# 14_NTC_TEMPSENSOR.net
KiCad netlist of a schematic drawn in Altium Designer
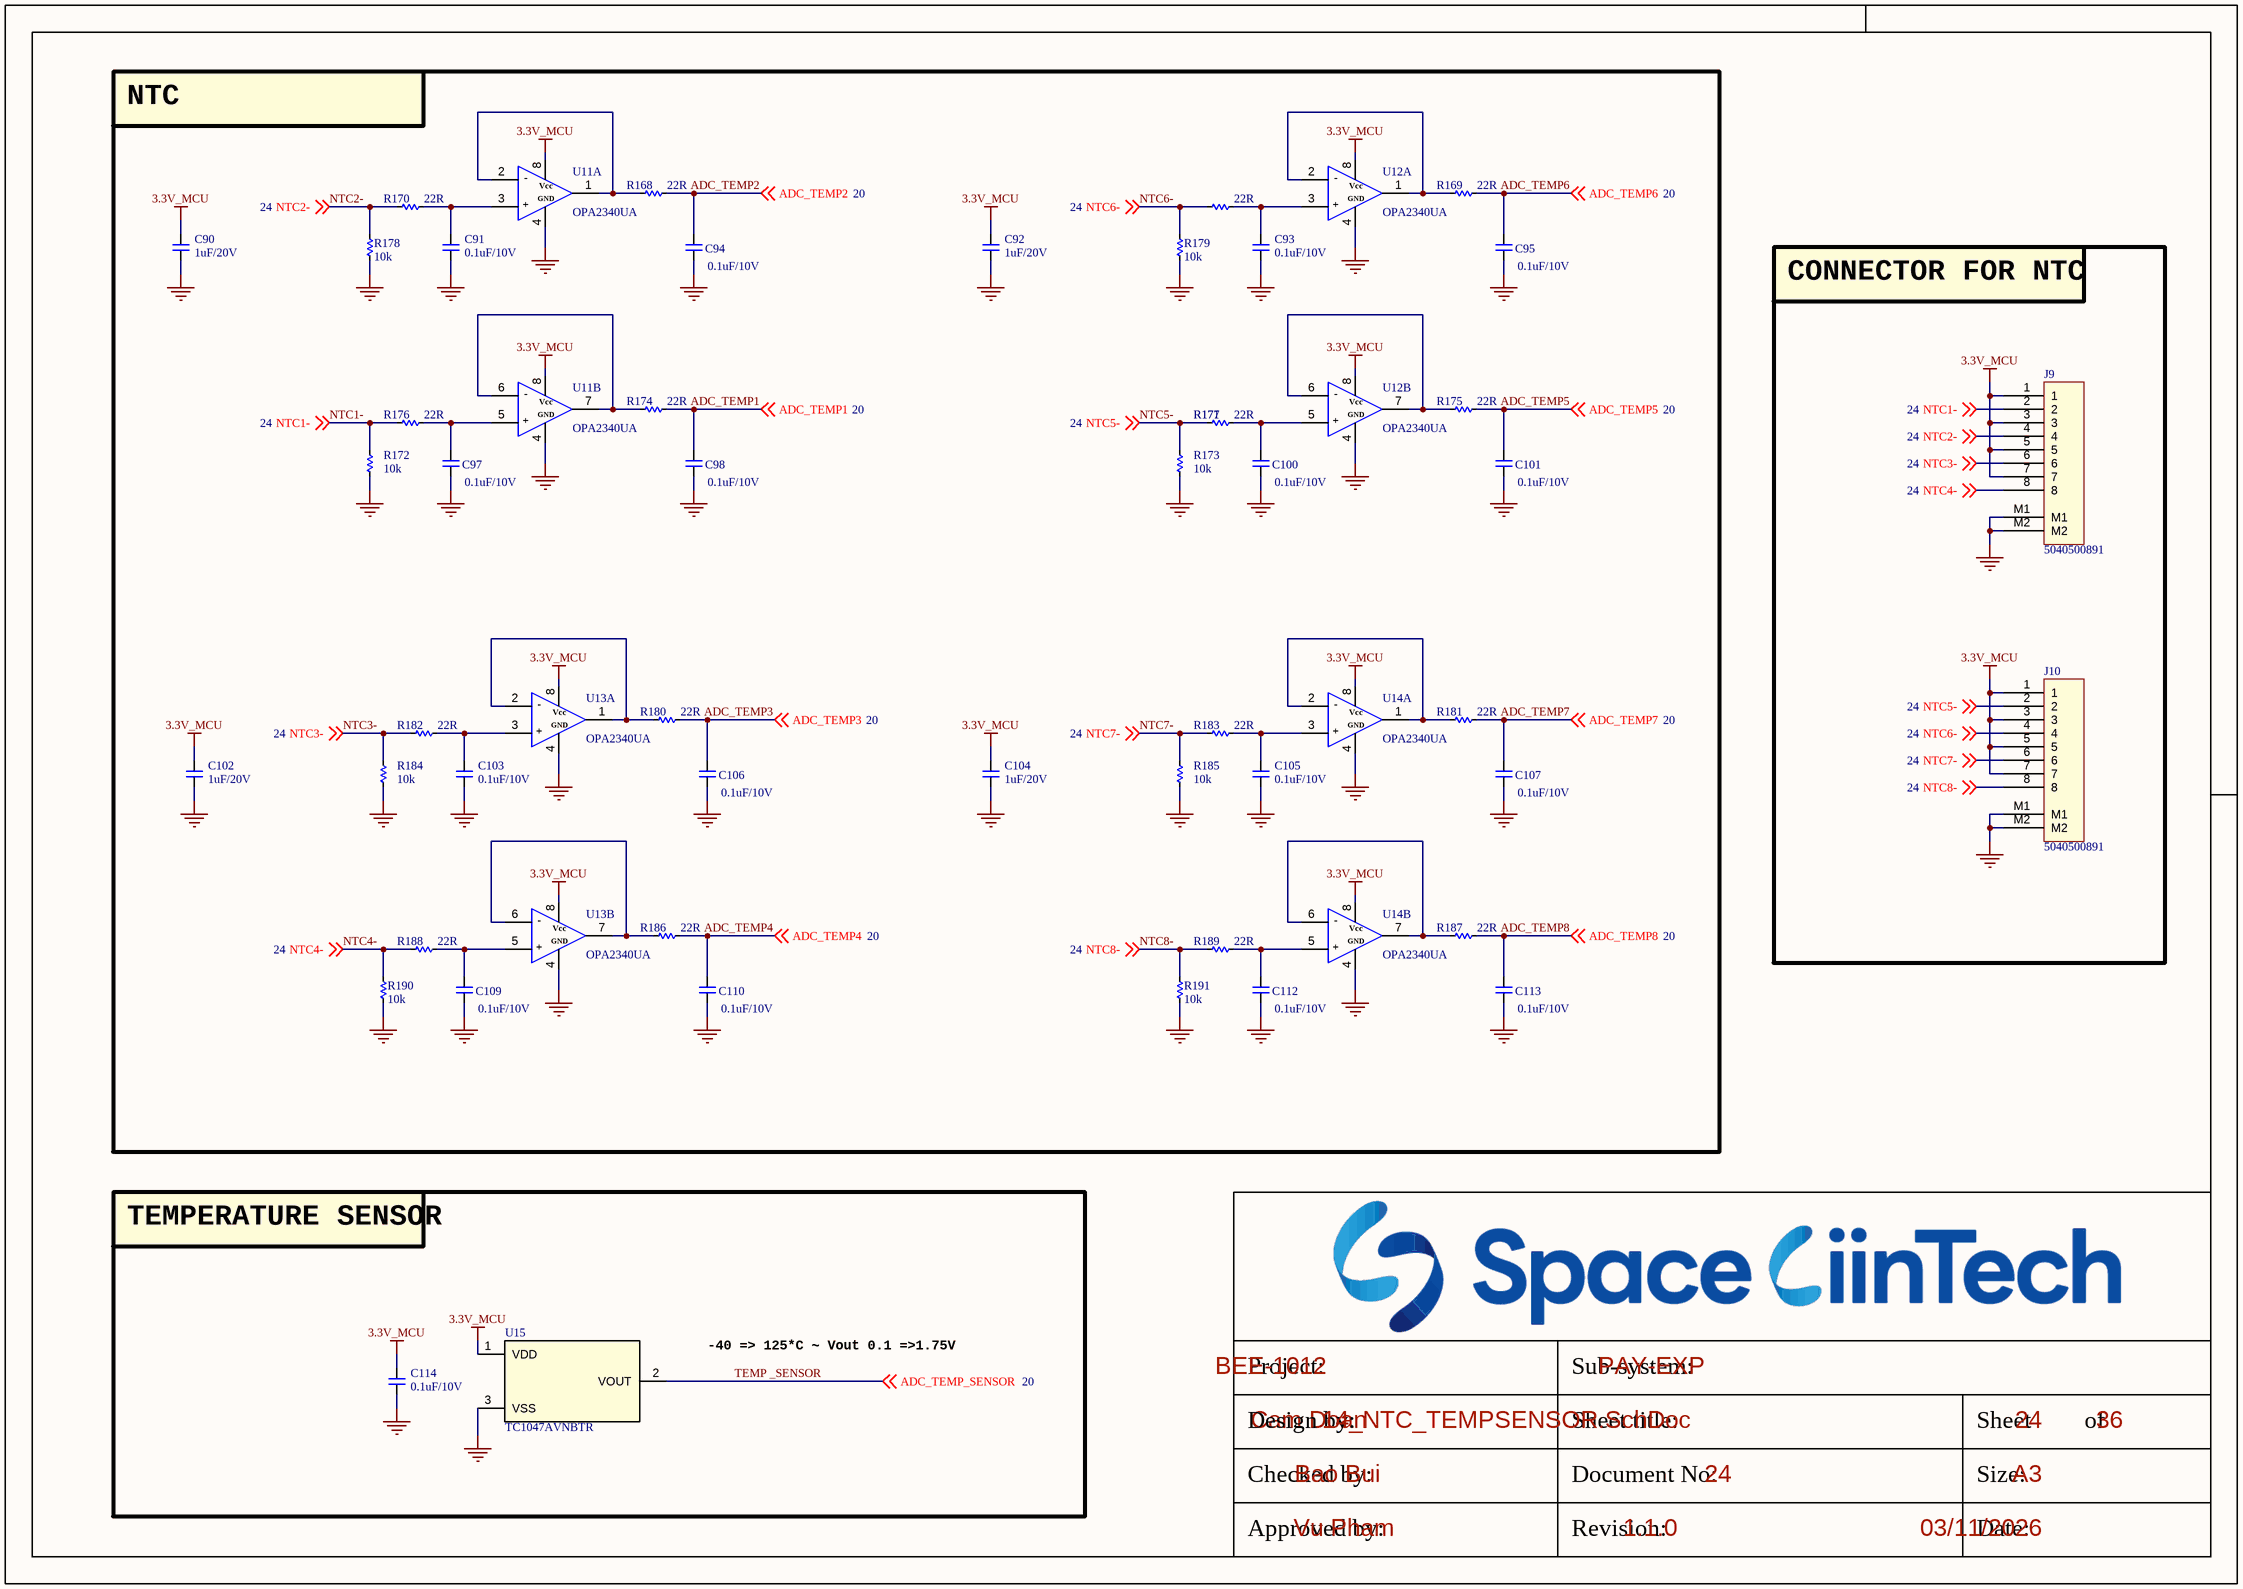
[diagram p0: 14_NTC_TEMPSENSOR.SchDoc]

(export (version "E")
  (design (tool "Eeschema 10.0.6"))
  (components
    (comp (ref "C90")
      (value "1uF/20V")
      (footprint "CAP_C_1005X50_L")
      (description "CAP")
      (libsource (lib "LABLIB") (part "_CAP_C_2"))
    )
    (comp (ref "C91")
      (value "0.1uF/10V")
      (footprint "CAP_C_1005X50_L")
      (description "CAP")
      (libsource (lib "LABLIB") (part "_CAP_C_2"))
    )
    (comp (ref "C92")
      (value "1uF/20V")
      (footprint "CAP_C_1005X50_L")
      (description "CAP")
      (libsource (lib "LABLIB") (part "_CAP_C_2"))
    )
    (comp (ref "C93")
      (value "0.1uF/10V")
      (footprint "CAP_C_1005X50_L")
      (description "CAP")
      (libsource (lib "LABLIB") (part "_CAP_C_2"))
    )
    (comp (ref "C94")
      (value "0.1uF/10V")
      (footprint "CAP_C_1005X50_L")
      (description "CAP")
      (libsource (lib "LABLIB") (part "_CAP_C_2"))
    )
    (comp (ref "C95")
      (value "0.1uF/10V")
      (footprint "CAP_C_1005X50_L")
      (description "CAP")
      (libsource (lib "LABLIB") (part "_CAP_C_2"))
    )
    (comp (ref "C97")
      (value "0.1uF/10V")
      (footprint "CAP_C_1005X50_L")
      (description "CAP")
      (libsource (lib "LABLIB") (part "_CAP_C_2"))
    )
    (comp (ref "C98")
      (value "0.1uF/10V")
      (footprint "CAP_C_1005X50_L")
      (description "CAP")
      (libsource (lib "LABLIB") (part "_CAP_C_2"))
    )
    (comp (ref "C100")
      (value "0.1uF/10V")
      (footprint "CAP_C_1005X50_L")
      (description "CAP")
      (libsource (lib "LABLIB") (part "_CAP_C_2"))
    )
    (comp (ref "C101")
      (value "0.1uF/10V")
      (footprint "CAP_C_1005X50_L")
      (description "CAP")
      (libsource (lib "LABLIB") (part "_CAP_C_2"))
    )
    (comp (ref "C102")
      (value "1uF/20V")
      (footprint "CAP_C_1005X50_L")
      (description "CAP")
      (libsource (lib "LABLIB") (part "_CAP_C_2"))
    )
    (comp (ref "C103")
      (value "0.1uF/10V")
      (footprint "CAP_C_1005X50_L")
      (description "CAP")
      (libsource (lib "LABLIB") (part "_CAP_C_2"))
    )
    (comp (ref "C104")
      (value "1uF/20V")
      (footprint "CAP_C_1005X50_L")
      (description "CAP")
      (libsource (lib "LABLIB") (part "_CAP_C_2"))
    )
    (comp (ref "C105")
      (value "0.1uF/10V")
      (footprint "CAP_C_1005X50_L")
      (description "CAP")
      (libsource (lib "LABLIB") (part "_CAP_C_2"))
    )
    (comp (ref "C106")
      (value "0.1uF/10V")
      (footprint "CAP_C_1005X50_L")
      (description "CAP")
      (libsource (lib "LABLIB") (part "_CAP_C_2"))
    )
    (comp (ref "C107")
      (value "0.1uF/10V")
      (footprint "CAP_C_1005X50_L")
      (description "CAP")
      (libsource (lib "LABLIB") (part "_CAP_C_2"))
    )
    (comp (ref "C109")
      (value "0.1uF/10V")
      (footprint "CAP_C_1005X50_L")
      (description "CAP")
      (libsource (lib "LABLIB") (part "_CAP_C_2"))
    )
    (comp (ref "C110")
      (value "0.1uF/10V")
      (footprint "CAP_C_1005X50_L")
      (description "CAP")
      (libsource (lib "LABLIB") (part "_CAP_C_2"))
    )
    (comp (ref "C112")
      (value "0.1uF/10V")
      (footprint "CAP_C_1005X50_L")
      (description "CAP")
      (libsource (lib "LABLIB") (part "_CAP_C_2"))
    )
    (comp (ref "C113")
      (value "0.1uF/10V")
      (footprint "CAP_C_1005X50_L")
      (description "CAP")
      (libsource (lib "LABLIB") (part "_CAP_C_2"))
    )
    (comp (ref "C114")
      (value "0.1uF/10V")
      (footprint "CAP_C_1005X50_L")
      (description "CAP")
      (libsource (lib "LABLIB") (part "_CAP_C_2"))
    )
    (comp (ref "J9")
      (value "5040500891")
      (footprint "MOLEX_5040500891")
      (libsource (lib "LABLIB") (part "Header 8x1_2M"))
    )
    (comp (ref "J10")
      (value "5040500891")
      (footprint "MOLEX_5040500891")
      (libsource (lib "LABLIB") (part "Header 8x1_2M"))
    )
    (comp (ref "R168")
      (value "22R")
      (footprint "RES_C_1005x30_L")
      (description "RES")
      (libsource (lib "LABLIB") (part "_RES_B_2"))
    )
    (comp (ref "R169")
      (value "22R")
      (footprint "RES_C_1005x30_L")
      (description "RES")
      (libsource (lib "LABLIB") (part "_RES_B_2"))
    )
    (comp (ref "R170")
      (value "22R")
      (footprint "RES_C_1005x30_L")
      (description "RES")
      (libsource (lib "LABLIB") (part "_RES_B_2"))
    )
    (comp (ref "R171")
      (value "22R")
      (footprint "RES_C_1005x30_L")
      (description "RES")
      (libsource (lib "LABLIB") (part "_RES_B_2"))
    )
    (comp (ref "R172")
      (value "10k")
      (footprint "RES_C_1005x30_L")
      (description "RES")
      (libsource (lib "LABLIB") (part "_RES_B_2"))
    )
    (comp (ref "R173")
      (value "10k")
      (footprint "RES_C_1005x30_L")
      (description "RES")
      (libsource (lib "LABLIB") (part "_RES_B_2"))
    )
    (comp (ref "R174")
      (value "22R")
      (footprint "RES_C_1005x30_L")
      (description "RES")
      (libsource (lib "LABLIB") (part "_RES_B_2"))
    )
    (comp (ref "R175")
      (value "22R")
      (footprint "RES_C_1005x30_L")
      (description "RES")
      (libsource (lib "LABLIB") (part "_RES_B_2"))
    )
    (comp (ref "R176")
      (value "22R")
      (footprint "RES_C_1005x30_L")
      (description "RES")
      (libsource (lib "LABLIB") (part "_RES_B_2"))
    )
    (comp (ref "R177")
      (value "22R")
      (footprint "RES_C_1005x30_L")
      (description "RES")
      (libsource (lib "LABLIB") (part "_RES_B_2"))
    )
    (comp (ref "R178")
      (value "10k")
      (footprint "RES_C_1005x30_L")
      (description "RES")
      (libsource (lib "LABLIB") (part "_RES_B_2"))
    )
    (comp (ref "R179")
      (value "10k")
      (footprint "RES_C_1005x30_L")
      (description "RES")
      (libsource (lib "LABLIB") (part "_RES_B_2"))
    )
    (comp (ref "R180")
      (value "22R")
      (footprint "RES_C_1005x30_L")
      (description "RES")
      (libsource (lib "LABLIB") (part "_RES_B_2"))
    )
    (comp (ref "R181")
      (value "22R")
      (footprint "RES_C_1005x30_L")
      (description "RES")
      (libsource (lib "LABLIB") (part "_RES_B_2"))
    )
    (comp (ref "R182")
      (value "22R")
      (footprint "RES_C_1005x30_L")
      (description "RES")
      (libsource (lib "LABLIB") (part "_RES_B_2"))
    )
    (comp (ref "R183")
      (value "22R")
      (footprint "RES_C_1005x30_L")
      (description "RES")
      (libsource (lib "LABLIB") (part "_RES_B_2"))
    )
    (comp (ref "R184")
      (value "10k")
      (footprint "RES_C_1005x30_L")
      (description "RES")
      (libsource (lib "LABLIB") (part "_RES_B_2"))
    )
    (comp (ref "R185")
      (value "10k")
      (footprint "RES_C_1005x30_L")
      (description "RES")
      (libsource (lib "LABLIB") (part "_RES_B_2"))
    )
    (comp (ref "R186")
      (value "22R")
      (footprint "RES_C_1005x30_L")
      (description "RES")
      (libsource (lib "LABLIB") (part "_RES_B_2"))
    )
    (comp (ref "R187")
      (value "22R")
      (footprint "RES_C_1005x30_L")
      (description "RES")
      (libsource (lib "LABLIB") (part "_RES_B_2"))
    )
    (comp (ref "R188")
      (value "22R")
      (footprint "RES_C_1005x30_L")
      (description "RES")
      (libsource (lib "LABLIB") (part "_RES_B_2"))
    )
    (comp (ref "R189")
      (value "22R")
      (footprint "RES_C_1005x30_L")
      (description "RES")
      (libsource (lib "LABLIB") (part "_RES_B_2"))
    )
    (comp (ref "R190")
      (value "10k")
      (footprint "RES_C_1005x30_L")
      (description "RES")
      (libsource (lib "LABLIB") (part "_RES_B_2"))
    )
    (comp (ref "R191")
      (value "10k")
      (footprint "RES_C_1005x30_L")
      (description "RES")
      (libsource (lib "LABLIB") (part "_RES_B_2"))
    )
    (comp (ref "U11")
      (value "OPA2340UA")
      (footprint "SOIC127P602X173-8N")
      (libsource (lib "EXP_HW_V3") (part "OPA2340UA"))
    )
    (comp (ref "U12")
      (value "OPA2340UA")
      (footprint "SOIC127P602X173-8N")
      (libsource (lib "EXP_HW_V3") (part "OPA2340UA"))
    )
    (comp (ref "U13")
      (value "OPA2340UA")
      (footprint "SOIC127P602X173-8N")
      (libsource (lib "EXP_HW_V3") (part "OPA2340UA"))
    )
    (comp (ref "U14")
      (value "OPA2340UA")
      (footprint "SOIC127P602X173-8N")
      (libsource (lib "EXP_HW_V3") (part "OPA2340UA"))
    )
    (comp (ref "U15")
      (value "TC1047AVNBTR")
      (footprint "SOT95P240X120-3N")
      (description "Temperature Sensor Analog, Local -40°C ~ 125°C 10mV/°C SOT-23-3")
      (libsource (lib "LABLIB") (part "IC_SENSOR_TC1047AVNBTR"))
    )
  )
  (nets
    (net (code "1") (name "3.3V_MCU") (class "Default")
      (node (ref "C102") (pin "2") (pinfunction "2_2") (pintype "passive"))
      (node (ref "C104") (pin "2") (pinfunction "2_2") (pintype "passive"))
      (node (ref "C114") (pin "2") (pinfunction "2_2") (pintype "passive"))
      (node (ref "C90") (pin "2") (pinfunction "2_2") (pintype "passive"))
      (node (ref "C92") (pin "2") (pinfunction "2_2") (pintype "passive"))
      (node (ref "J10") (pin "1") (pinfunction "1_1") (pintype "passive"))
      (node (ref "J10") (pin "3") (pinfunction "3_3") (pintype "passive"))
      (node (ref "J10") (pin "5") (pinfunction "5_5") (pintype "passive"))
      (node (ref "J10") (pin "7") (pinfunction "7_7") (pintype "passive"))
      (node (ref "J9") (pin "1") (pinfunction "1_1") (pintype "passive"))
      (node (ref "J9") (pin "3") (pinfunction "3_3") (pintype "passive"))
      (node (ref "J9") (pin "5") (pinfunction "5_5") (pintype "passive"))
      (node (ref "J9") (pin "7") (pinfunction "7_7") (pintype "passive"))
      (node (ref "U11") (pin "8") (pinfunction "8_8") (pintype "passive"))
      (node (ref "U12") (pin "8") (pinfunction "8_8") (pintype "passive"))
      (node (ref "U13") (pin "8") (pinfunction "8_8") (pintype "passive"))
      (node (ref "U14") (pin "8") (pinfunction "8_8") (pintype "passive"))
      (node (ref "U15") (pin "1") (pinfunction "VDD_1") (pintype "passive"))
    )
    (net (code "2") (name "ADC_TEMP1") (class "Default")
      (node (ref "C98") (pin "2") (pinfunction "2_2") (pintype "passive"))
      (node (ref "R174") (pin "2") (pinfunction "2_2") (pintype "passive"))
    )
    (net (code "3") (name "ADC_TEMP2") (class "Default")
      (node (ref "C94") (pin "2") (pinfunction "2_2") (pintype "passive"))
      (node (ref "R168") (pin "2") (pinfunction "2_2") (pintype "passive"))
    )
    (net (code "4") (name "ADC_TEMP3") (class "Default")
      (node (ref "C106") (pin "2") (pinfunction "2_2") (pintype "passive"))
      (node (ref "R180") (pin "2") (pinfunction "2_2") (pintype "passive"))
    )
    (net (code "5") (name "ADC_TEMP4") (class "Default")
      (node (ref "C110") (pin "2") (pinfunction "2_2") (pintype "passive"))
      (node (ref "R186") (pin "2") (pinfunction "2_2") (pintype "passive"))
    )
    (net (code "6") (name "ADC_TEMP5") (class "Default")
      (node (ref "C101") (pin "2") (pinfunction "2_2") (pintype "passive"))
      (node (ref "R175") (pin "2") (pinfunction "2_2") (pintype "passive"))
    )
    (net (code "7") (name "ADC_TEMP6") (class "Default")
      (node (ref "C95") (pin "2") (pinfunction "2_2") (pintype "passive"))
      (node (ref "R169") (pin "2") (pinfunction "2_2") (pintype "passive"))
    )
    (net (code "8") (name "ADC_TEMP7") (class "Default")
      (node (ref "C107") (pin "2") (pinfunction "2_2") (pintype "passive"))
      (node (ref "R181") (pin "2") (pinfunction "2_2") (pintype "passive"))
    )
    (net (code "9") (name "ADC_TEMP8") (class "Default")
      (node (ref "C113") (pin "2") (pinfunction "2_2") (pintype "passive"))
      (node (ref "R187") (pin "2") (pinfunction "2_2") (pintype "passive"))
    )
    (net (code "10") (name "ADC_TEMP_SENSOR") (class "Default")
      (node (ref "U15") (pin "2") (pinfunction "VOUT_2") (pintype "passive"))
    )
    (net (code "11") (name "GND") (class "Default")
      (node (ref "C100") (pin "1") (pinfunction "1_1") (pintype "passive"))
      (node (ref "C101") (pin "1") (pinfunction "1_1") (pintype "passive"))
      (node (ref "C102") (pin "1") (pinfunction "1_1") (pintype "passive"))
      (node (ref "C103") (pin "1") (pinfunction "1_1") (pintype "passive"))
      (node (ref "C104") (pin "1") (pinfunction "1_1") (pintype "passive"))
      (node (ref "C105") (pin "1") (pinfunction "1_1") (pintype "passive"))
      (node (ref "C106") (pin "1") (pinfunction "1_1") (pintype "passive"))
      (node (ref "C107") (pin "1") (pinfunction "1_1") (pintype "passive"))
      (node (ref "C109") (pin "1") (pinfunction "1_1") (pintype "passive"))
      (node (ref "C110") (pin "1") (pinfunction "1_1") (pintype "passive"))
      (node (ref "C112") (pin "1") (pinfunction "1_1") (pintype "passive"))
      (node (ref "C113") (pin "1") (pinfunction "1_1") (pintype "passive"))
      (node (ref "C114") (pin "1") (pinfunction "1_1") (pintype "passive"))
      (node (ref "C90") (pin "1") (pinfunction "1_1") (pintype "passive"))
      (node (ref "C91") (pin "1") (pinfunction "1_1") (pintype "passive"))
      (node (ref "C92") (pin "1") (pinfunction "1_1") (pintype "passive"))
      (node (ref "C93") (pin "1") (pinfunction "1_1") (pintype "passive"))
      (node (ref "C94") (pin "1") (pinfunction "1_1") (pintype "passive"))
      (node (ref "C95") (pin "1") (pinfunction "1_1") (pintype "passive"))
      (node (ref "C97") (pin "1") (pinfunction "1_1") (pintype "passive"))
      (node (ref "C98") (pin "1") (pinfunction "1_1") (pintype "passive"))
      (node (ref "J10") (pin "M1") (pinfunction "M1_M1") (pintype "passive"))
      (node (ref "J10") (pin "M2") (pinfunction "M2_M2") (pintype "passive"))
      (node (ref "J9") (pin "M1") (pinfunction "M1_M1") (pintype "passive"))
      (node (ref "J9") (pin "M2") (pinfunction "M2_M2") (pintype "passive"))
      (node (ref "R172") (pin "1") (pinfunction "1_1") (pintype "passive"))
      (node (ref "R173") (pin "1") (pinfunction "1_1") (pintype "passive"))
      (node (ref "R178") (pin "1") (pinfunction "1_1") (pintype "passive"))
      (node (ref "R179") (pin "1") (pinfunction "1_1") (pintype "passive"))
      (node (ref "R184") (pin "1") (pinfunction "1_1") (pintype "passive"))
      (node (ref "R185") (pin "1") (pinfunction "1_1") (pintype "passive"))
      (node (ref "R190") (pin "1") (pinfunction "1_1") (pintype "passive"))
      (node (ref "R191") (pin "1") (pinfunction "1_1") (pintype "passive"))
      (node (ref "U11") (pin "4") (pinfunction "4_4") (pintype "passive"))
      (node (ref "U12") (pin "4") (pinfunction "4_4") (pintype "passive"))
      (node (ref "U13") (pin "4") (pinfunction "4_4") (pintype "passive"))
      (node (ref "U14") (pin "4") (pinfunction "4_4") (pintype "passive"))
      (node (ref "U15") (pin "3") (pinfunction "VSS_3") (pintype "passive"))
    )
    (net (code "12") (name "NTC1-") (class "Default")
      (node (ref "J9") (pin "2") (pinfunction "2_2") (pintype "passive"))
      (node (ref "R172") (pin "2") (pinfunction "2_2") (pintype "passive"))
      (node (ref "R176") (pin "1") (pinfunction "1_1") (pintype "passive"))
    )
    (net (code "13") (name "NTC2-") (class "Default")
      (node (ref "J9") (pin "4") (pinfunction "4_4") (pintype "passive"))
      (node (ref "R170") (pin "1") (pinfunction "1_1") (pintype "passive"))
      (node (ref "R178") (pin "2") (pinfunction "2_2") (pintype "passive"))
    )
    (net (code "14") (name "NTC3-") (class "Default")
      (node (ref "J9") (pin "6") (pinfunction "6_6") (pintype "passive"))
      (node (ref "R182") (pin "1") (pinfunction "1_1") (pintype "passive"))
      (node (ref "R184") (pin "2") (pinfunction "2_2") (pintype "passive"))
    )
    (net (code "15") (name "NTC4-") (class "Default")
      (node (ref "J9") (pin "8") (pinfunction "8_8") (pintype "passive"))
      (node (ref "R188") (pin "1") (pinfunction "1_1") (pintype "passive"))
      (node (ref "R190") (pin "2") (pinfunction "2_2") (pintype "passive"))
    )
    (net (code "16") (name "NTC5-") (class "Default")
      (node (ref "J10") (pin "2") (pinfunction "2_2") (pintype "passive"))
      (node (ref "R173") (pin "2") (pinfunction "2_2") (pintype "passive"))
      (node (ref "R177") (pin "1") (pinfunction "1_1") (pintype "passive"))
    )
    (net (code "17") (name "NTC6-") (class "Default")
      (node (ref "J10") (pin "4") (pinfunction "4_4") (pintype "passive"))
      (node (ref "R171") (pin "1") (pinfunction "1_1") (pintype "passive"))
      (node (ref "R179") (pin "2") (pinfunction "2_2") (pintype "passive"))
    )
    (net (code "18") (name "NTC7-") (class "Default")
      (node (ref "J10") (pin "6") (pinfunction "6_6") (pintype "passive"))
      (node (ref "R183") (pin "1") (pinfunction "1_1") (pintype "passive"))
      (node (ref "R185") (pin "2") (pinfunction "2_2") (pintype "passive"))
    )
    (net (code "19") (name "NTC8-") (class "Default")
      (node (ref "J10") (pin "8") (pinfunction "8_8") (pintype "passive"))
      (node (ref "R189") (pin "1") (pinfunction "1_1") (pintype "passive"))
      (node (ref "R191") (pin "2") (pinfunction "2_2") (pintype "passive"))
    )
    (net (code "20") (name "Net-(C91-Pad2)") (class "Default")
      (node (ref "C91") (pin "2") (pinfunction "2_2") (pintype "passive"))
      (node (ref "R170") (pin "2") (pinfunction "2_2") (pintype "passive"))
      (node (ref "U11") (pin "3") (pinfunction "3_3") (pintype "passive"))
    )
    (net (code "21") (name "Net-(C93-Pad2)") (class "Default")
      (node (ref "C93") (pin "2") (pinfunction "2_2") (pintype "passive"))
      (node (ref "R171") (pin "2") (pinfunction "2_2") (pintype "passive"))
      (node (ref "U12") (pin "3") (pinfunction "3_3") (pintype "passive"))
    )
    (net (code "22") (name "Net-(C97-Pad2)") (class "Default")
      (node (ref "C97") (pin "2") (pinfunction "2_2") (pintype "passive"))
      (node (ref "R176") (pin "2") (pinfunction "2_2") (pintype "passive"))
      (node (ref "U11") (pin "5") (pinfunction "5_5") (pintype "passive"))
    )
    (net (code "23") (name "Net-(C100-Pad2)") (class "Default")
      (node (ref "C100") (pin "2") (pinfunction "2_2") (pintype "passive"))
      (node (ref "R177") (pin "2") (pinfunction "2_2") (pintype "passive"))
      (node (ref "U12") (pin "5") (pinfunction "5_5") (pintype "passive"))
    )
    (net (code "24") (name "Net-(C103-Pad2)") (class "Default")
      (node (ref "C103") (pin "2") (pinfunction "2_2") (pintype "passive"))
      (node (ref "R182") (pin "2") (pinfunction "2_2") (pintype "passive"))
      (node (ref "U13") (pin "3") (pinfunction "3_3") (pintype "passive"))
    )
    (net (code "25") (name "Net-(C105-Pad2)") (class "Default")
      (node (ref "C105") (pin "2") (pinfunction "2_2") (pintype "passive"))
      (node (ref "R183") (pin "2") (pinfunction "2_2") (pintype "passive"))
      (node (ref "U14") (pin "3") (pinfunction "3_3") (pintype "passive"))
    )
    (net (code "26") (name "Net-(C109-Pad2)") (class "Default")
      (node (ref "C109") (pin "2") (pinfunction "2_2") (pintype "passive"))
      (node (ref "R188") (pin "2") (pinfunction "2_2") (pintype "passive"))
      (node (ref "U13") (pin "5") (pinfunction "5_5") (pintype "passive"))
    )
    (net (code "27") (name "Net-(C112-Pad2)") (class "Default")
      (node (ref "C112") (pin "2") (pinfunction "2_2") (pintype "passive"))
      (node (ref "R189") (pin "2") (pinfunction "2_2") (pintype "passive"))
      (node (ref "U14") (pin "5") (pinfunction "5_5") (pintype "passive"))
    )
    (net (code "28") (name "Net-(R168-Pad1)") (class "Default")
      (node (ref "R168") (pin "1") (pinfunction "1_1") (pintype "passive"))
      (node (ref "U11") (pin "1") (pinfunction "1_1") (pintype "passive"))
      (node (ref "U11") (pin "2") (pinfunction "2_2") (pintype "passive"))
    )
    (net (code "29") (name "Net-(R169-Pad1)") (class "Default")
      (node (ref "R169") (pin "1") (pinfunction "1_1") (pintype "passive"))
      (node (ref "U12") (pin "1") (pinfunction "1_1") (pintype "passive"))
      (node (ref "U12") (pin "2") (pinfunction "2_2") (pintype "passive"))
    )
    (net (code "30") (name "Net-(R174-Pad1)") (class "Default")
      (node (ref "R174") (pin "1") (pinfunction "1_1") (pintype "passive"))
      (node (ref "U11") (pin "6") (pinfunction "6_6") (pintype "passive"))
      (node (ref "U11") (pin "7") (pinfunction "7_7") (pintype "passive"))
    )
    (net (code "31") (name "Net-(R175-Pad1)") (class "Default")
      (node (ref "R175") (pin "1") (pinfunction "1_1") (pintype "passive"))
      (node (ref "U12") (pin "6") (pinfunction "6_6") (pintype "passive"))
      (node (ref "U12") (pin "7") (pinfunction "7_7") (pintype "passive"))
    )
    (net (code "32") (name "Net-(R180-Pad1)") (class "Default")
      (node (ref "R180") (pin "1") (pinfunction "1_1") (pintype "passive"))
      (node (ref "U13") (pin "1") (pinfunction "1_1") (pintype "passive"))
      (node (ref "U13") (pin "2") (pinfunction "2_2") (pintype "passive"))
    )
    (net (code "33") (name "Net-(R181-Pad1)") (class "Default")
      (node (ref "R181") (pin "1") (pinfunction "1_1") (pintype "passive"))
      (node (ref "U14") (pin "1") (pinfunction "1_1") (pintype "passive"))
      (node (ref "U14") (pin "2") (pinfunction "2_2") (pintype "passive"))
    )
    (net (code "34") (name "Net-(R186-Pad1)") (class "Default")
      (node (ref "R186") (pin "1") (pinfunction "1_1") (pintype "passive"))
      (node (ref "U13") (pin "6") (pinfunction "6_6") (pintype "passive"))
      (node (ref "U13") (pin "7") (pinfunction "7_7") (pintype "passive"))
    )
    (net (code "35") (name "Net-(R187-Pad1)") (class "Default")
      (node (ref "R187") (pin "1") (pinfunction "1_1") (pintype "passive"))
      (node (ref "U14") (pin "6") (pinfunction "6_6") (pintype "passive"))
      (node (ref "U14") (pin "7") (pinfunction "7_7") (pintype "passive"))
    )
  )
)
